# ConnectorBoard.net
KiCad netlist of a schematic drawn in EAGLE
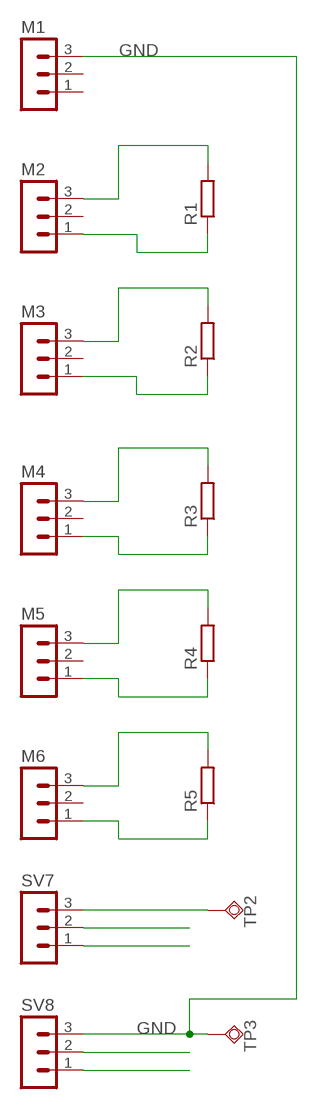
[diagram p0: schematic, sheet 1]

(export (version "E")
  (design (tool "Eeschema 10.0.6"))
  (components
    (comp (ref "M1")
      (value "MA03-1")
      (footprint "eagle-import:MA03-1")
      (libsource (lib "eagle-import") (part "MA03-1"))
    )
    (comp (ref "M2")
      (value "MA03-1")
      (footprint "eagle-import:MA03-1")
      (libsource (lib "eagle-import") (part "MA03-1"))
    )
    (comp (ref "M3")
      (value "MA03-1")
      (footprint "eagle-import:MA03-1")
      (libsource (lib "eagle-import") (part "MA03-1"))
    )
    (comp (ref "M4")
      (value "MA03-1")
      (footprint "eagle-import:MA03-1")
      (libsource (lib "eagle-import") (part "MA03-1"))
    )
    (comp (ref "M5")
      (value "MA03-1")
      (footprint "eagle-import:MA03-1")
      (libsource (lib "eagle-import") (part "MA03-1"))
    )
    (comp (ref "M6")
      (value "MA03-1")
      (footprint "eagle-import:MA03-1")
      (libsource (lib "eagle-import") (part "MA03-1"))
    )
    (comp (ref "R1")
      (value "R-EU_R0402")
      (footprint "eagle-import:R0402")
      (libsource (lib "eagle-import") (part "R-EU_R0402"))
    )
    (comp (ref "R2")
      (value "R-EU_R0402")
      (footprint "eagle-import:R0402")
      (libsource (lib "eagle-import") (part "R-EU_R0402"))
    )
    (comp (ref "R3")
      (value "R-EU_R0402")
      (footprint "eagle-import:R0402")
      (libsource (lib "eagle-import") (part "R-EU_R0402"))
    )
    (comp (ref "R4")
      (value "R-EU_R0402")
      (footprint "eagle-import:R0402")
      (libsource (lib "eagle-import") (part "R-EU_R0402"))
    )
    (comp (ref "R5")
      (value "R-EU_R0402")
      (footprint "eagle-import:R0402")
      (libsource (lib "eagle-import") (part "R-EU_R0402"))
    )
    (comp (ref "SV7")
      (value "MA03-1")
      (footprint "eagle-import:MA03-1")
      (libsource (lib "eagle-import") (part "MA03-1"))
    )
    (comp (ref "SV8")
      (value "MA03-1")
      (footprint "eagle-import:MA03-1")
      (libsource (lib "eagle-import") (part "MA03-1"))
    )
    (comp (ref "TP2")
      (value "TPSQTP14SQ")
      (footprint "eagle-import:TP14SQ")
      (libsource (lib "eagle-import") (part "TPSQTP14SQ"))
    )
    (comp (ref "TP3")
      (value "TPSQTP14SQ")
      (footprint "eagle-import:TP14SQ")
      (libsource (lib "eagle-import") (part "TPSQTP14SQ"))
    )
  )
  (nets
    (net (code "1") (name "/GND") (class "Default")
      (node (ref "M1") (pin "3") (pinfunction "3_3") (pintype "passive"))
      (node (ref "SV8") (pin "3") (pinfunction "3_3") (pintype "passive"))
      (node (ref "TP3") (pin "TP") (pinfunction "TP_TP") (pintype "input"))
    )
    (net (code "2") (name "Net-(M2-Pad1)") (class "Default")
      (node (ref "M2") (pin "1") (pinfunction "1_1") (pintype "passive"))
      (node (ref "R1") (pin "1") (pinfunction "1_1") (pintype "passive"))
    )
    (net (code "3") (name "Net-(M2-Pad3)") (class "Default")
      (node (ref "M2") (pin "3") (pinfunction "3_3") (pintype "passive"))
      (node (ref "R1") (pin "2") (pinfunction "2_2") (pintype "passive"))
    )
    (net (code "4") (name "Net-(M3-Pad1)") (class "Default")
      (node (ref "M3") (pin "1") (pinfunction "1_1") (pintype "passive"))
      (node (ref "R2") (pin "1") (pinfunction "1_1") (pintype "passive"))
    )
    (net (code "5") (name "Net-(M3-Pad3)") (class "Default")
      (node (ref "M3") (pin "3") (pinfunction "3_3") (pintype "passive"))
      (node (ref "R2") (pin "2") (pinfunction "2_2") (pintype "passive"))
    )
    (net (code "6") (name "Net-(M4-Pad1)") (class "Default")
      (node (ref "M4") (pin "1") (pinfunction "1_1") (pintype "passive"))
      (node (ref "R3") (pin "1") (pinfunction "1_1") (pintype "passive"))
    )
    (net (code "7") (name "Net-(M4-Pad3)") (class "Default")
      (node (ref "M4") (pin "3") (pinfunction "3_3") (pintype "passive"))
      (node (ref "R3") (pin "2") (pinfunction "2_2") (pintype "passive"))
    )
    (net (code "8") (name "Net-(M5-Pad1)") (class "Default")
      (node (ref "M5") (pin "1") (pinfunction "1_1") (pintype "passive"))
      (node (ref "R4") (pin "1") (pinfunction "1_1") (pintype "passive"))
    )
    (net (code "9") (name "Net-(M5-Pad3)") (class "Default")
      (node (ref "M5") (pin "3") (pinfunction "3_3") (pintype "passive"))
      (node (ref "R4") (pin "2") (pinfunction "2_2") (pintype "passive"))
    )
    (net (code "10") (name "Net-(M6-Pad1)") (class "Default")
      (node (ref "M6") (pin "1") (pinfunction "1_1") (pintype "passive"))
      (node (ref "R5") (pin "1") (pinfunction "1_1") (pintype "passive"))
    )
    (net (code "11") (name "Net-(M6-Pad3)") (class "Default")
      (node (ref "M6") (pin "3") (pinfunction "3_3") (pintype "passive"))
      (node (ref "R5") (pin "2") (pinfunction "2_2") (pintype "passive"))
    )
    (net (code "12") (name "Net-(SV7-Pad3)") (class "Default")
      (node (ref "SV7") (pin "3") (pinfunction "3_3") (pintype "passive"))
      (node (ref "TP2") (pin "TP") (pinfunction "TP_TP") (pintype "input"))
    )
    (net (code "13") (name "unconnected-(M1-Pad1)") (class "Default")
      (node (ref "M1") (pin "1") (pinfunction "1_1") (pintype "passive"))
    )
    (net (code "14") (name "unconnected-(M1-Pad2)") (class "Default")
      (node (ref "M1") (pin "2") (pinfunction "2_2") (pintype "passive"))
    )
    (net (code "15") (name "unconnected-(M2-Pad2)") (class "Default")
      (node (ref "M2") (pin "2") (pinfunction "2_2") (pintype "passive"))
    )
    (net (code "16") (name "unconnected-(M3-Pad2)") (class "Default")
      (node (ref "M3") (pin "2") (pinfunction "2_2") (pintype "passive"))
    )
    (net (code "17") (name "unconnected-(M4-Pad2)") (class "Default")
      (node (ref "M4") (pin "2") (pinfunction "2_2") (pintype "passive"))
    )
    (net (code "18") (name "unconnected-(M5-Pad2)") (class "Default")
      (node (ref "M5") (pin "2") (pinfunction "2_2") (pintype "passive"))
    )
    (net (code "19") (name "unconnected-(M6-Pad2)") (class "Default")
      (node (ref "M6") (pin "2") (pinfunction "2_2") (pintype "passive"))
    )
    (net (code "20") (name "unconnected-(SV7-Pad1)") (class "Default")
      (node (ref "SV7") (pin "1") (pinfunction "1_1") (pintype "passive"))
    )
    (net (code "21") (name "unconnected-(SV7-Pad2)") (class "Default")
      (node (ref "SV7") (pin "2") (pinfunction "2_2") (pintype "passive"))
    )
    (net (code "22") (name "unconnected-(SV8-Pad1)") (class "Default")
      (node (ref "SV8") (pin "1") (pinfunction "1_1") (pintype "passive"))
    )
    (net (code "23") (name "unconnected-(SV8-Pad2)") (class "Default")
      (node (ref "SV8") (pin "2") (pinfunction "2_2") (pintype "passive"))
    )
  )
)
